# heptaphasis.net
KiCad netlist of a schematic drawn in EAGLE
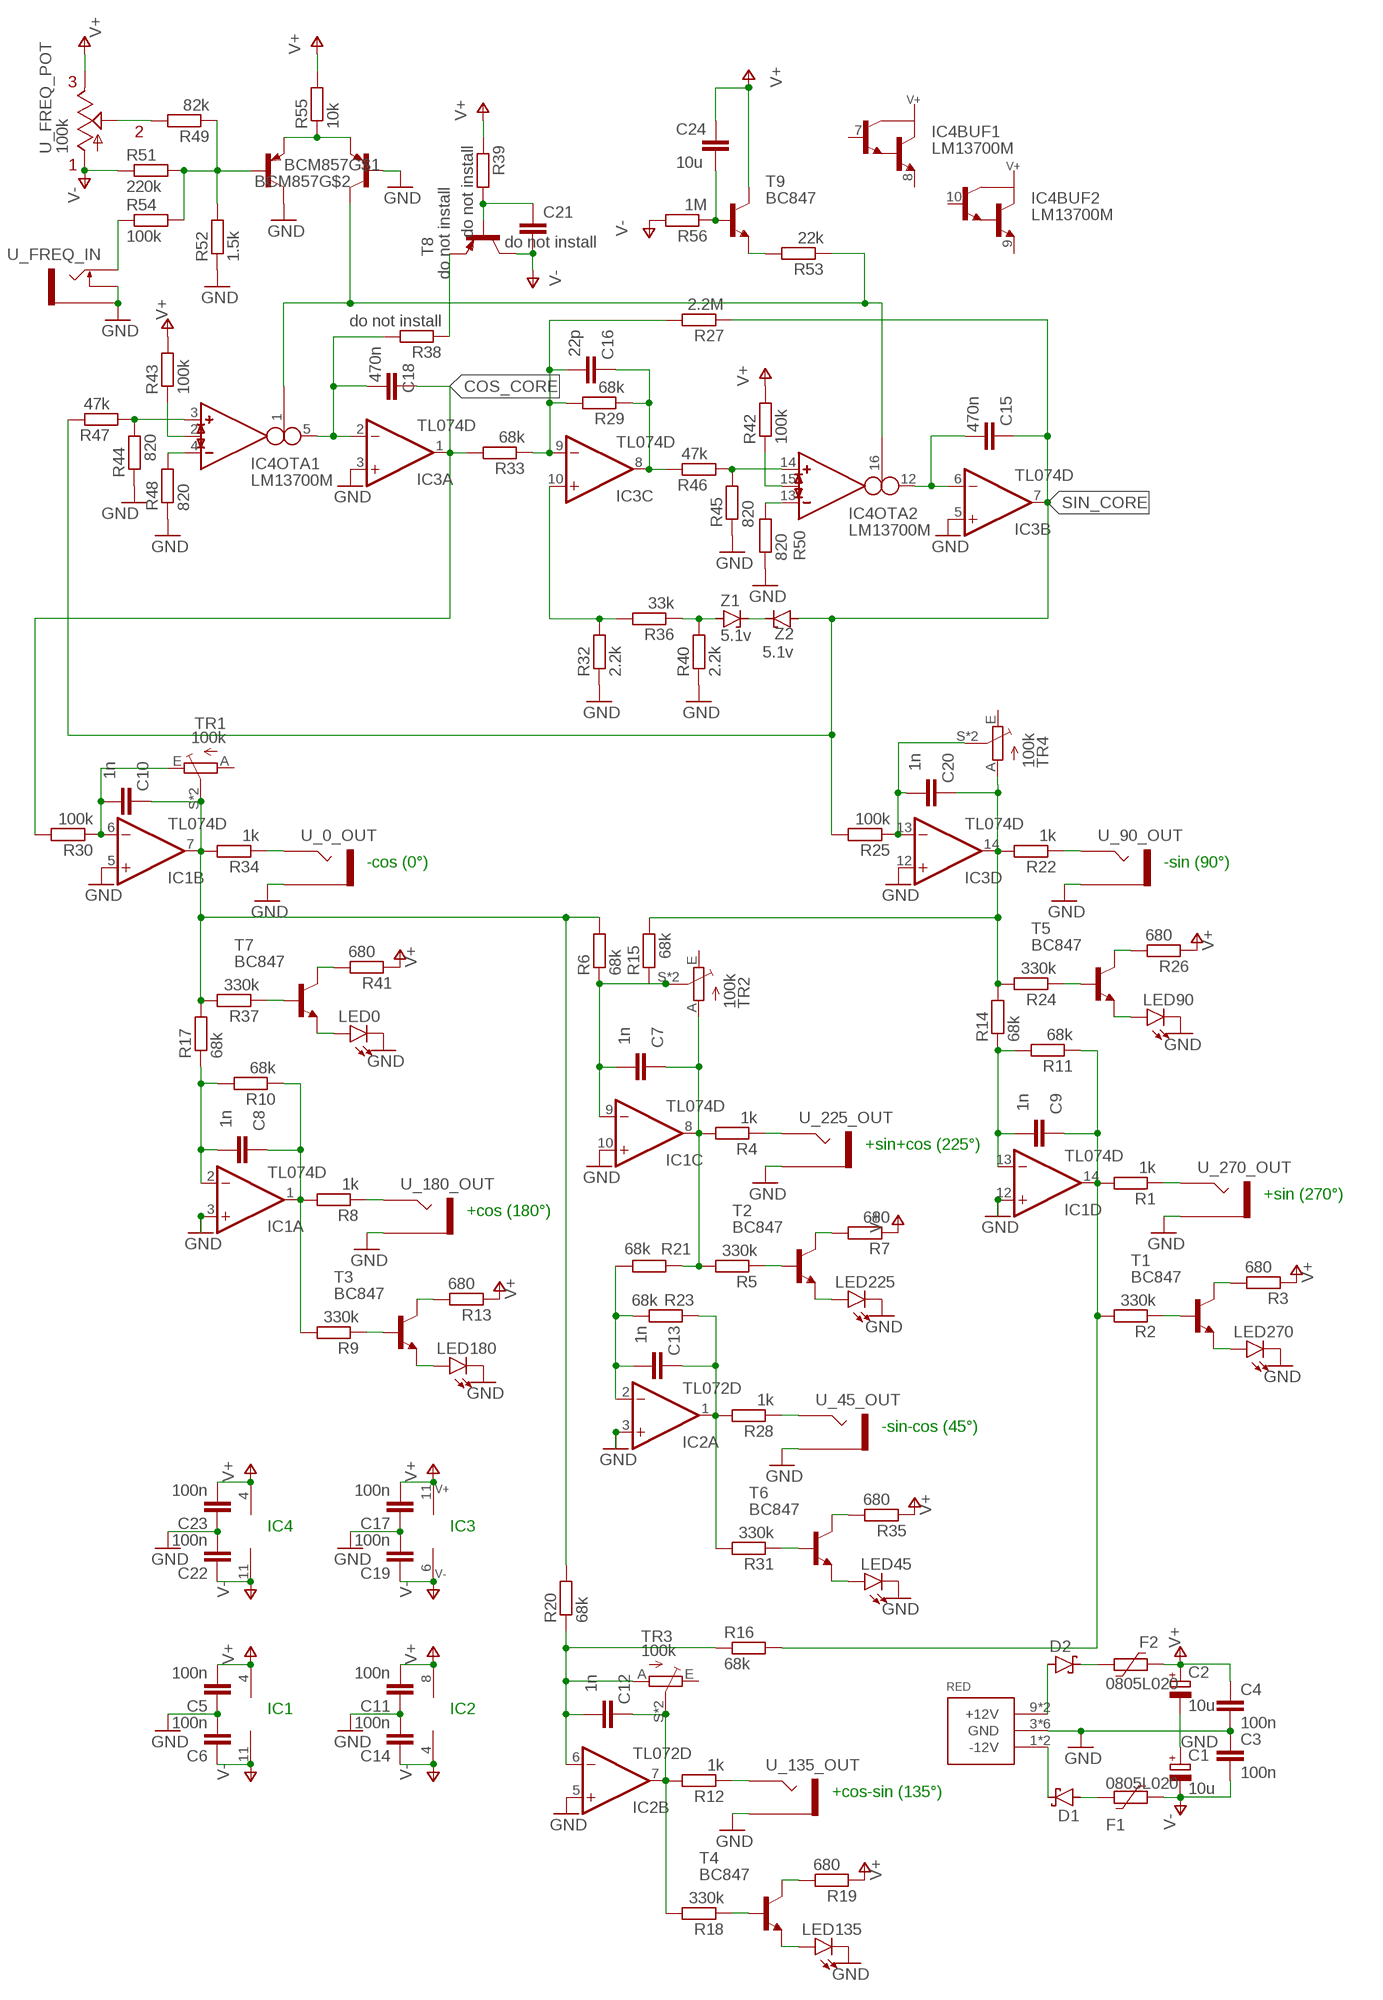
[diagram p0: schematic, sheet 1]

(export (version "E")
  (design (tool "Eeschema 10.0.6"))
  (components
    (comp (ref "BCM857")
      (value "BCM857DS")
      (footprint "eagle-import:SOT457R_PHILIPS")
      (libsource (lib "eagle-import") (part "BCM857DS"))
    )
    (comp (ref "C1")
      (value "10u")
      (footprint "eagle-import:E2-5")
      (libsource (lib "eagle-import") (part "CPOL-EUE2-5"))
    )
    (comp (ref "C2")
      (value "10u")
      (footprint "eagle-import:E2-5")
      (libsource (lib "eagle-import") (part "CPOL-EUE2-5"))
    )
    (comp (ref "C3")
      (value "100n")
      (footprint "eagle-import:C0805")
      (libsource (lib "eagle-import") (part "C-EUC0805"))
    )
    (comp (ref "C4")
      (value "100n")
      (footprint "eagle-import:C0805")
      (libsource (lib "eagle-import") (part "C-EUC0805"))
    )
    (comp (ref "C5")
      (value "100n")
      (footprint "eagle-import:C0805")
      (libsource (lib "eagle-import") (part "C-EUC0805"))
    )
    (comp (ref "C6")
      (value "100n")
      (footprint "eagle-import:C0805")
      (libsource (lib "eagle-import") (part "C-EUC0805"))
    )
    (comp (ref "C7")
      (value "1n")
      (footprint "eagle-import:C0805")
      (libsource (lib "eagle-import") (part "C-EUC0805"))
    )
    (comp (ref "C8")
      (value "1n")
      (footprint "eagle-import:C0805")
      (libsource (lib "eagle-import") (part "C-EUC0805"))
    )
    (comp (ref "C9")
      (value "1n")
      (footprint "eagle-import:C0805")
      (libsource (lib "eagle-import") (part "C-EUC0805"))
    )
    (comp (ref "C10")
      (value "1n")
      (footprint "eagle-import:C0805")
      (libsource (lib "eagle-import") (part "C-EUC0805"))
    )
    (comp (ref "C11")
      (value "100n")
      (footprint "eagle-import:C0805")
      (libsource (lib "eagle-import") (part "C-EUC0805"))
    )
    (comp (ref "C12")
      (value "1n")
      (footprint "eagle-import:C0805")
      (libsource (lib "eagle-import") (part "C-EUC0805"))
    )
    (comp (ref "C13")
      (value "1n")
      (footprint "eagle-import:C0805")
      (libsource (lib "eagle-import") (part "C-EUC0805"))
    )
    (comp (ref "C14")
      (value "100n")
      (footprint "eagle-import:C0805")
      (libsource (lib "eagle-import") (part "C-EUC0805"))
    )
    (comp (ref "C15")
      (value "470n")
      (footprint "eagle-import:C0805")
      (libsource (lib "eagle-import") (part "C-EUC0805"))
    )
    (comp (ref "C16")
      (value "22p")
      (footprint "eagle-import:C0805")
      (libsource (lib "eagle-import") (part "C-EUC0805"))
    )
    (comp (ref "C17")
      (value "100n")
      (footprint "eagle-import:C0805")
      (libsource (lib "eagle-import") (part "C-EUC0805"))
    )
    (comp (ref "C18")
      (value "470n")
      (footprint "eagle-import:C0805")
      (libsource (lib "eagle-import") (part "C-EUC0805"))
    )
    (comp (ref "C19")
      (value "100n")
      (footprint "eagle-import:C0805")
      (libsource (lib "eagle-import") (part "C-EUC0805"))
    )
    (comp (ref "C20")
      (value "1n")
      (footprint "eagle-import:C0805")
      (libsource (lib "eagle-import") (part "C-EUC0805"))
    )
    (comp (ref "C21")
      (value "do not install")
      (footprint "eagle-import:C0805")
      (libsource (lib "eagle-import") (part "C-EUC0805"))
    )
    (comp (ref "C22")
      (value "100n")
      (footprint "eagle-import:C0805")
      (libsource (lib "eagle-import") (part "C-EUC0805"))
    )
    (comp (ref "C23")
      (value "100n")
      (footprint "eagle-import:C0805")
      (libsource (lib "eagle-import") (part "C-EUC0805"))
    )
    (comp (ref "C24")
      (value "10u")
      (footprint "eagle-import:C0805")
      (libsource (lib "eagle-import") (part "C-EUC0805"))
    )
    (comp (ref "D1")
      (value "VERTICAL_SCHOTTKY")
      (footprint "eagle-import:DO41-7")
      (libsource (lib "eagle-import") (part "VERTICAL_SCHOTTKY"))
    )
    (comp (ref "D2")
      (value "VERTICAL_SCHOTTKY")
      (footprint "eagle-import:DO41-7")
      (libsource (lib "eagle-import") (part "VERTICAL_SCHOTTKY"))
    )
    (comp (ref "F1")
      (value "0805L020")
      (footprint "eagle-import:0805L")
      (fields (field (name "MF") "Littelfuse"))
      (libsource (lib "eagle-import") (part "?0805L020"))
    )
    (comp (ref "F2")
      (value "0805L020")
      (footprint "eagle-import:0805L")
      (fields (field (name "MF") "Littelfuse"))
      (libsource (lib "eagle-import") (part "?0805L020"))
    )
    (comp (ref "IC1")
      (value "TL074D")
      (footprint "eagle-import:SO14")
      (libsource (lib "eagle-import") (part "TL074D"))
    )
    (comp (ref "IC2")
      (value "TL072D")
      (footprint "eagle-import:SO08")
      (libsource (lib "eagle-import") (part "TL072D"))
    )
    (comp (ref "IC3")
      (value "TL074D")
      (footprint "eagle-import:SO14")
      (libsource (lib "eagle-import") (part "TL074D"))
    )
    (comp (ref "IC4")
      (value "LM13700M")
      (footprint "eagle-import:SO16")
      (libsource (lib "eagle-import") (part "LM13700M"))
    )
    (comp (ref "LED0")
      (value "LED3MM")
      (footprint "eagle-import:LED3MM")
      (libsource (lib "eagle-import") (part "LED3MM"))
    )
    (comp (ref "LED45")
      (value "LED3MM")
      (footprint "eagle-import:LED3MM")
      (libsource (lib "eagle-import") (part "LED3MM"))
    )
    (comp (ref "LED90")
      (value "LED3MM")
      (footprint "eagle-import:LED3MM")
      (libsource (lib "eagle-import") (part "LED3MM"))
    )
    (comp (ref "LED135")
      (value "LED3MM")
      (footprint "eagle-import:LED3MM")
      (libsource (lib "eagle-import") (part "LED3MM"))
    )
    (comp (ref "LED180")
      (value "LED3MM")
      (footprint "eagle-import:LED3MM")
      (libsource (lib "eagle-import") (part "LED3MM"))
    )
    (comp (ref "LED225")
      (value "LED3MM")
      (footprint "eagle-import:LED3MM")
      (libsource (lib "eagle-import") (part "LED3MM"))
    )
    (comp (ref "LED270")
      (value "LED3MM")
      (footprint "eagle-import:LED3MM")
      (libsource (lib "eagle-import") (part "LED3MM"))
    )
    (comp (ref "R1")
      (value "1k")
      (footprint "eagle-import:R0805")
      (libsource (lib "eagle-import") (part "R-EU_R0805"))
    )
    (comp (ref "R2")
      (value "330k")
      (footprint "eagle-import:R0805")
      (libsource (lib "eagle-import") (part "R-EU_R0805"))
    )
    (comp (ref "R3")
      (value "680")
      (footprint "eagle-import:R0805")
      (libsource (lib "eagle-import") (part "R-EU_R0805"))
    )
    (comp (ref "R4")
      (value "1k")
      (footprint "eagle-import:R0805")
      (libsource (lib "eagle-import") (part "R-EU_R0805"))
    )
    (comp (ref "R5")
      (value "330k")
      (footprint "eagle-import:R0805")
      (libsource (lib "eagle-import") (part "R-EU_R0805"))
    )
    (comp (ref "R6")
      (value "68k")
      (footprint "eagle-import:R0805")
      (libsource (lib "eagle-import") (part "R-EU_R0805"))
    )
    (comp (ref "R7")
      (value "680")
      (footprint "eagle-import:R0805")
      (libsource (lib "eagle-import") (part "R-EU_R0805"))
    )
    (comp (ref "R8")
      (value "1k")
      (footprint "eagle-import:R0805")
      (libsource (lib "eagle-import") (part "R-EU_R0805"))
    )
    (comp (ref "R9")
      (value "330k")
      (footprint "eagle-import:R0805")
      (libsource (lib "eagle-import") (part "R-EU_R0805"))
    )
    (comp (ref "R10")
      (value "68k")
      (footprint "eagle-import:R0805")
      (libsource (lib "eagle-import") (part "R-EU_R0805"))
    )
    (comp (ref "R11")
      (value "68k")
      (footprint "eagle-import:R0805")
      (libsource (lib "eagle-import") (part "R-EU_R0805"))
    )
    (comp (ref "R12")
      (value "1k")
      (footprint "eagle-import:R0805")
      (libsource (lib "eagle-import") (part "R-EU_R0805"))
    )
    (comp (ref "R13")
      (value "680")
      (footprint "eagle-import:R0805")
      (libsource (lib "eagle-import") (part "R-EU_R0805"))
    )
    (comp (ref "R14")
      (value "68k")
      (footprint "eagle-import:R0805")
      (libsource (lib "eagle-import") (part "R-EU_R0805"))
    )
    (comp (ref "R15")
      (value "68k")
      (footprint "eagle-import:R0805")
      (libsource (lib "eagle-import") (part "R-EU_R0805"))
    )
    (comp (ref "R16")
      (value "68k")
      (footprint "eagle-import:R0805")
      (libsource (lib "eagle-import") (part "R-EU_R0805"))
    )
    (comp (ref "R17")
      (value "68k")
      (footprint "eagle-import:R0805")
      (libsource (lib "eagle-import") (part "R-EU_R0805"))
    )
    (comp (ref "R18")
      (value "330k")
      (footprint "eagle-import:R0805")
      (libsource (lib "eagle-import") (part "R-EU_R0805"))
    )
    (comp (ref "R19")
      (value "680")
      (footprint "eagle-import:R0805")
      (libsource (lib "eagle-import") (part "R-EU_R0805"))
    )
    (comp (ref "R20")
      (value "68k")
      (footprint "eagle-import:R0805")
      (libsource (lib "eagle-import") (part "R-EU_R0805"))
    )
    (comp (ref "R21")
      (value "68k")
      (footprint "eagle-import:R0805")
      (libsource (lib "eagle-import") (part "R-EU_R0805"))
    )
    (comp (ref "R22")
      (value "1k")
      (footprint "eagle-import:R0805")
      (libsource (lib "eagle-import") (part "R-EU_R0805"))
    )
    (comp (ref "R23")
      (value "68k")
      (footprint "eagle-import:R0805")
      (libsource (lib "eagle-import") (part "R-EU_R0805"))
    )
    (comp (ref "R24")
      (value "330k")
      (footprint "eagle-import:R0805")
      (libsource (lib "eagle-import") (part "R-EU_R0805"))
    )
    (comp (ref "R25")
      (value "100k")
      (footprint "eagle-import:R0805")
      (libsource (lib "eagle-import") (part "R-EU_R0805"))
    )
    (comp (ref "R26")
      (value "680")
      (footprint "eagle-import:R0805")
      (libsource (lib "eagle-import") (part "R-EU_R0805"))
    )
    (comp (ref "R27")
      (value "2.2M")
      (footprint "eagle-import:R0805")
      (libsource (lib "eagle-import") (part "R-EU_R0805"))
    )
    (comp (ref "R28")
      (value "1k")
      (footprint "eagle-import:R0805")
      (libsource (lib "eagle-import") (part "R-EU_R0805"))
    )
    (comp (ref "R29")
      (value "68k")
      (footprint "eagle-import:R0805")
      (libsource (lib "eagle-import") (part "R-EU_R0805"))
    )
    (comp (ref "R30")
      (value "100k")
      (footprint "eagle-import:R0805")
      (libsource (lib "eagle-import") (part "R-EU_R0805"))
    )
    (comp (ref "R31")
      (value "330k")
      (footprint "eagle-import:R0805")
      (libsource (lib "eagle-import") (part "R-EU_R0805"))
    )
    (comp (ref "R32")
      (value "2.2k")
      (footprint "eagle-import:R0805")
      (libsource (lib "eagle-import") (part "R-EU_R0805"))
    )
    (comp (ref "R33")
      (value "68k")
      (footprint "eagle-import:R0805")
      (libsource (lib "eagle-import") (part "R-EU_R0805"))
    )
    (comp (ref "R34")
      (value "1k")
      (footprint "eagle-import:R0805")
      (libsource (lib "eagle-import") (part "R-EU_R0805"))
    )
    (comp (ref "R35")
      (value "680")
      (footprint "eagle-import:R0805")
      (libsource (lib "eagle-import") (part "R-EU_R0805"))
    )
    (comp (ref "R36")
      (value "33k")
      (footprint "eagle-import:R0805")
      (libsource (lib "eagle-import") (part "R-EU_R0805"))
    )
    (comp (ref "R37")
      (value "330k")
      (footprint "eagle-import:R0805")
      (libsource (lib "eagle-import") (part "R-EU_R0805"))
    )
    (comp (ref "R38")
      (value "do not install")
      (footprint "eagle-import:R0805")
      (libsource (lib "eagle-import") (part "R-EU_R0805"))
    )
    (comp (ref "R39")
      (value "do not install")
      (footprint "eagle-import:R0805")
      (libsource (lib "eagle-import") (part "R-EU_R0805"))
    )
    (comp (ref "R40")
      (value "2.2k")
      (footprint "eagle-import:R0805")
      (libsource (lib "eagle-import") (part "R-EU_R0805"))
    )
    (comp (ref "R41")
      (value "680")
      (footprint "eagle-import:R0805")
      (libsource (lib "eagle-import") (part "R-EU_R0805"))
    )
    (comp (ref "R42")
      (value "100k")
      (footprint "eagle-import:R0805")
      (libsource (lib "eagle-import") (part "R-EU_R0805"))
    )
    (comp (ref "R43")
      (value "100k")
      (footprint "eagle-import:R0805")
      (libsource (lib "eagle-import") (part "R-EU_R0805"))
    )
    (comp (ref "R44")
      (value "820")
      (footprint "eagle-import:R0805")
      (libsource (lib "eagle-import") (part "R-EU_R0805"))
    )
    (comp (ref "R45")
      (value "820")
      (footprint "eagle-import:R0805")
      (libsource (lib "eagle-import") (part "R-EU_R0805"))
    )
    (comp (ref "R46")
      (value "47k")
      (footprint "eagle-import:R0805")
      (libsource (lib "eagle-import") (part "R-EU_R0805"))
    )
    (comp (ref "R47")
      (value "47k")
      (footprint "eagle-import:R0805")
      (libsource (lib "eagle-import") (part "R-EU_R0805"))
    )
    (comp (ref "R48")
      (value "820")
      (footprint "eagle-import:R0805")
      (libsource (lib "eagle-import") (part "R-EU_R0805"))
    )
    (comp (ref "R49")
      (value "82k")
      (footprint "eagle-import:R0805")
      (libsource (lib "eagle-import") (part "R-EU_R0805"))
    )
    (comp (ref "R50")
      (value "820")
      (footprint "eagle-import:R0805")
      (libsource (lib "eagle-import") (part "R-EU_R0805"))
    )
    (comp (ref "R51")
      (value "220k")
      (footprint "eagle-import:R0805")
      (libsource (lib "eagle-import") (part "R-EU_R0805"))
    )
    (comp (ref "R52")
      (value "1.5k")
      (footprint "eagle-import:R0805")
      (libsource (lib "eagle-import") (part "R-EU_R0805"))
    )
    (comp (ref "R53")
      (value "22k")
      (footprint "eagle-import:R0805")
      (libsource (lib "eagle-import") (part "R-EU_R0805"))
    )
    (comp (ref "R54")
      (value "100k")
      (footprint "eagle-import:R0805")
      (libsource (lib "eagle-import") (part "R-EU_R0805"))
    )
    (comp (ref "R55")
      (value "10k")
      (footprint "eagle-import:R0805")
      (libsource (lib "eagle-import") (part "R-EU_R0805"))
    )
    (comp (ref "R56")
      (value "1M")
      (footprint "eagle-import:R0805")
      (libsource (lib "eagle-import") (part "R-EU_R0805"))
    )
    (comp (ref "RED")
      (value "POWER_SIMPLE10")
      (footprint "eagle-import:POWER_10")
      (fields (field (name "SPICEPREFIX") "U"))
      (libsource (lib "eagle-import") (part "POWER_SIMPLE10"))
    )
    (comp (ref "T1")
      (value "BC847")
      (footprint "eagle-import:SOT23")
      (libsource (lib "eagle-import") (part "BC847"))
    )
    (comp (ref "T2")
      (value "BC847")
      (footprint "eagle-import:SOT23")
      (libsource (lib "eagle-import") (part "BC847"))
    )
    (comp (ref "T3")
      (value "BC847")
      (footprint "eagle-import:SOT23")
      (libsource (lib "eagle-import") (part "BC847"))
    )
    (comp (ref "T4")
      (value "BC847")
      (footprint "eagle-import:SOT23")
      (libsource (lib "eagle-import") (part "BC847"))
    )
    (comp (ref "T5")
      (value "BC847")
      (footprint "eagle-import:SOT23")
      (libsource (lib "eagle-import") (part "BC847"))
    )
    (comp (ref "T6")
      (value "BC847")
      (footprint "eagle-import:SOT23")
      (libsource (lib "eagle-import") (part "BC847"))
    )
    (comp (ref "T7")
      (value "BC847")
      (footprint "eagle-import:SOT23")
      (libsource (lib "eagle-import") (part "BC847"))
    )
    (comp (ref "T8")
      (value "do not install")
      (footprint "eagle-import:SOT23")
      (libsource (lib "eagle-import") (part "BC857"))
    )
    (comp (ref "T9")
      (value "BC847")
      (footprint "eagle-import:SOT23")
      (libsource (lib "eagle-import") (part "BC847"))
    )
    (comp (ref "TR1")
      (value "100k")
      (footprint "eagle-import:S64YW")
      (libsource (lib "eagle-import") (part "MULTITURN_TRIMPOT_DUAL_FOOTPRINTS64YW"))
    )
    (comp (ref "TR2")
      (value "100k")
      (footprint "eagle-import:S64YW")
      (libsource (lib "eagle-import") (part "MULTITURN_TRIMPOT_DUAL_FOOTPRINTS64YW"))
    )
    (comp (ref "TR3")
      (value "100k")
      (footprint "eagle-import:S64YW")
      (libsource (lib "eagle-import") (part "MULTITURN_TRIMPOT_DUAL_FOOTPRINTS64YW"))
    )
    (comp (ref "TR4")
      (value "100k")
      (footprint "eagle-import:S64YW")
      (libsource (lib "eagle-import") (part "MULTITURN_TRIMPOT_DUAL_FOOTPRINTS64YW"))
    )
    (comp (ref "U_0_OUT")
      (value "PJ302M_NO_NORM")
      (footprint "eagle-import:PJ302M_NO_NORM")
      (libsource (lib "eagle-import") (part "PJ302M_NO_NORM"))
    )
    (comp (ref "U_45_OUT")
      (value "PJ302M_NO_NORM")
      (footprint "eagle-import:PJ302M_NO_NORM")
      (libsource (lib "eagle-import") (part "PJ302M_NO_NORM"))
    )
    (comp (ref "U_90_OUT")
      (value "PJ302M_NO_NORM")
      (footprint "eagle-import:PJ302M_NO_NORM")
      (libsource (lib "eagle-import") (part "PJ302M_NO_NORM"))
    )
    (comp (ref "U_135_OUT")
      (value "PJ302M_NO_NORM")
      (footprint "eagle-import:PJ302M_NO_NORM")
      (libsource (lib "eagle-import") (part "PJ302M_NO_NORM"))
    )
    (comp (ref "U_180_OUT")
      (value "PJ302M_NO_NORM")
      (footprint "eagle-import:PJ302M_NO_NORM")
      (libsource (lib "eagle-import") (part "PJ302M_NO_NORM"))
    )
    (comp (ref "U_225_OUT")
      (value "PJ302M_NO_NORM")
      (footprint "eagle-import:PJ302M_NO_NORM")
      (libsource (lib "eagle-import") (part "PJ302M_NO_NORM"))
    )
    (comp (ref "U_270_OUT")
      (value "PJ302M_NO_NORM")
      (footprint "eagle-import:PJ302M_NO_NORM")
      (libsource (lib "eagle-import") (part "PJ302M_NO_NORM"))
    )
    (comp (ref "U_FREQ_IN")
      (value "PJ302M")
      (footprint "eagle-import:PJ302M")
      (libsource (lib "eagle-import") (part "PJ302M"))
    )
    (comp (ref "U_FREQ_POT")
      (value "100k")
      (footprint "eagle-import:RK097-SINGLE-ELEMENT")
      (libsource (lib "eagle-import") (part "RK097-SINGLE"))
    )
    (comp (ref "Z1")
      (value "5.1v")
      (footprint "eagle-import:SOD80C")
      (libsource (lib "eagle-import") (part "ZENER-DIODESOD80C"))
    )
    (comp (ref "Z2")
      (value "5.1v")
      (footprint "eagle-import:SOD80C")
      (libsource (lib "eagle-import") (part "ZENER-DIODESOD80C"))
    )
  )
  (nets
    (net (code "1") (name "COS_CORE") (class "Default")
      (node (ref "C18") (pin "1") (pinfunction "1_1") (pintype "passive"))
      (node (ref "IC3") (pin "1") (pinfunction "OUT_1") (pintype "output"))
      (node (ref "R30") (pin "2") (pinfunction "2_2") (pintype "passive"))
      (node (ref "R33") (pin "2") (pinfunction "2_2") (pintype "passive"))
    )
    (net (code "2") (name "GND") (class "Default")
      (node (ref "BCM857") (pin "5") (pinfunction "B_5") (pintype "passive"))
      (node (ref "BCM857") (pin "6") (pinfunction "C_6") (pintype "passive"))
      (node (ref "C1") (pin "+") (pinfunction "+_+") (pintype "passive"))
      (node (ref "C11") (pin "1") (pinfunction "1_1") (pintype "passive"))
      (node (ref "C14") (pin "2") (pinfunction "2_2") (pintype "passive"))
      (node (ref "C17") (pin "1") (pinfunction "1_1") (pintype "passive"))
      (node (ref "C19") (pin "2") (pinfunction "2_2") (pintype "passive"))
      (node (ref "C2") (pin "-") (pinfunction "-_-") (pintype "passive"))
      (node (ref "C22") (pin "2") (pinfunction "2_2") (pintype "passive"))
      (node (ref "C23") (pin "1") (pinfunction "1_1") (pintype "passive"))
      (node (ref "C3") (pin "1") (pinfunction "1_1") (pintype "passive"))
      (node (ref "C4") (pin "2") (pinfunction "2_2") (pintype "passive"))
      (node (ref "C5") (pin "1") (pinfunction "1_1") (pintype "passive"))
      (node (ref "C6") (pin "2") (pinfunction "2_2") (pintype "passive"))
      (node (ref "IC1") (pin "10") (pinfunction "+IN_10") (pintype "input"))
      (node (ref "IC1") (pin "12") (pinfunction "+IN_12") (pintype "input"))
      (node (ref "IC1") (pin "3") (pinfunction "+IN_3") (pintype "input"))
      (node (ref "IC1") (pin "5") (pinfunction "+IN_5") (pintype "input"))
      (node (ref "IC2") (pin "3") (pinfunction "+IN_3") (pintype "input"))
      (node (ref "IC2") (pin "5") (pinfunction "+IN_5") (pintype "input"))
      (node (ref "IC3") (pin "12") (pinfunction "+IN_12") (pintype "input"))
      (node (ref "IC3") (pin "3") (pinfunction "+IN_3") (pintype "input"))
      (node (ref "IC3") (pin "5") (pinfunction "+IN_5") (pintype "input"))
      (node (ref "LED0") (pin "K") (pinfunction "C_K") (pintype "passive"))
      (node (ref "LED135") (pin "K") (pinfunction "C_K") (pintype "passive"))
      (node (ref "LED180") (pin "K") (pinfunction "C_K") (pintype "passive"))
      (node (ref "LED225") (pin "K") (pinfunction "C_K") (pintype "passive"))
      (node (ref "LED270") (pin "K") (pinfunction "C_K") (pintype "passive"))
      (node (ref "LED45") (pin "K") (pinfunction "C_K") (pintype "passive"))
      (node (ref "LED90") (pin "K") (pinfunction "C_K") (pintype "passive"))
      (node (ref "R32") (pin "1") (pinfunction "1_1") (pintype "passive"))
      (node (ref "R40") (pin "1") (pinfunction "1_1") (pintype "passive"))
      (node (ref "R44") (pin "1") (pinfunction "1_1") (pintype "passive"))
      (node (ref "R45") (pin "1") (pinfunction "1_1") (pintype "passive"))
      (node (ref "R48") (pin "1") (pinfunction "1_1") (pintype "passive"))
      (node (ref "R50") (pin "1") (pinfunction "1_1") (pintype "passive"))
      (node (ref "R52") (pin "1") (pinfunction "1_1") (pintype "passive"))
      (node (ref "RED") (pin "3") (pinfunction "GND_3") (pintype "bidirectional"))
      (node (ref "RED") (pin "4") (pinfunction "GND_4") (pintype "bidirectional"))
      (node (ref "RED") (pin "5") (pinfunction "GND_5") (pintype "bidirectional"))
      (node (ref "RED") (pin "6") (pinfunction "GND_6") (pintype "bidirectional"))
      (node (ref "RED") (pin "7") (pinfunction "GND_7") (pintype "bidirectional"))
      (node (ref "RED") (pin "8") (pinfunction "GND_8") (pintype "bidirectional"))
      (node (ref "U_0_OUT") (pin "GND") (pinfunction "SLEEVE_GND") (pintype "passive"))
      (node (ref "U_135_OUT") (pin "GND") (pinfunction "SLEEVE_GND") (pintype "passive"))
      (node (ref "U_180_OUT") (pin "GND") (pinfunction "SLEEVE_GND") (pintype "passive"))
      (node (ref "U_225_OUT") (pin "GND") (pinfunction "SLEEVE_GND") (pintype "passive"))
      (node (ref "U_270_OUT") (pin "GND") (pinfunction "SLEEVE_GND") (pintype "passive"))
      (node (ref "U_45_OUT") (pin "GND") (pinfunction "SLEEVE_GND") (pintype "passive"))
      (node (ref "U_90_OUT") (pin "GND") (pinfunction "SLEEVE_GND") (pintype "passive"))
      (node (ref "U_FREQ_IN") (pin "GND") (pinfunction "SLEEVE_GND") (pintype "passive"))
      (node (ref "U_FREQ_IN") (pin "SW") (pinfunction "SWITCH_SW") (pintype "passive"))
    )
    (net (code "3") (name "Net-(BCM857A-B)") (class "Default")
      (node (ref "BCM857") (pin "2") (pinfunction "B_2") (pintype "passive"))
      (node (ref "R49") (pin "1") (pinfunction "1_1") (pintype "passive"))
      (node (ref "R51") (pin "2") (pinfunction "2_2") (pintype "passive"))
      (node (ref "R52") (pin "2") (pinfunction "2_2") (pintype "passive"))
      (node (ref "R54") (pin "2") (pinfunction "2_2") (pintype "passive"))
    )
    (net (code "4") (name "Net-(BCM857A-E)") (class "Default")
      (node (ref "BCM857") (pin "1") (pinfunction "E_1") (pintype "passive"))
      (node (ref "BCM857") (pin "4") (pinfunction "E_4") (pintype "passive"))
      (node (ref "R55") (pin "1") (pinfunction "1_1") (pintype "passive"))
    )
    (net (code "5") (name "Net-(BCM857B-C)") (class "Default")
      (node (ref "BCM857") (pin "3") (pinfunction "C_3") (pintype "passive"))
      (node (ref "IC4") (pin "1") (pinfunction "I_BIAS_1") (pintype "input"))
      (node (ref "IC4") (pin "16") (pinfunction "I_BIAS_16") (pintype "input"))
      (node (ref "R53") (pin "1") (pinfunction "1_1") (pintype "passive"))
    )
    (net (code "6") (name "Net-(D1-PadA)") (class "Default")
      (node (ref "D1") (pin "A") (pinfunction "A_A") (pintype "passive"))
      (node (ref "F1") (pin "2") (pinfunction "2_2") (pintype "passive"))
    )
    (net (code "7") (name "Net-(D1-PadC)") (class "Default")
      (node (ref "D1") (pin "C") (pinfunction "C_C") (pintype "passive"))
      (node (ref "RED") (pin "1") (pinfunction "-12V_1") (pintype "bidirectional"))
      (node (ref "RED") (pin "2") (pinfunction "-12V_2") (pintype "bidirectional"))
    )
    (net (code "8") (name "Net-(D2-PadA)") (class "Default")
      (node (ref "D2") (pin "A") (pinfunction "A_A") (pintype "passive"))
      (node (ref "RED") (pin "10") (pinfunction "+12V_10") (pintype "bidirectional"))
      (node (ref "RED") (pin "9") (pinfunction "+12V_9") (pintype "bidirectional"))
    )
    (net (code "9") (name "Net-(D2-PadC)") (class "Default")
      (node (ref "D2") (pin "C") (pinfunction "C_C") (pintype "passive"))
      (node (ref "F2") (pin "2") (pinfunction "2_2") (pintype "passive"))
    )
    (net (code "10") (name "Net-(IC1A--IN)") (class "Default")
      (node (ref "C8") (pin "2") (pinfunction "2_2") (pintype "passive"))
      (node (ref "IC1") (pin "2") (pinfunction "-IN_2") (pintype "input"))
      (node (ref "R10") (pin "2") (pinfunction "2_2") (pintype "passive"))
      (node (ref "R17") (pin "1") (pinfunction "1_1") (pintype "passive"))
    )
    (net (code "11") (name "Net-(IC1A-OUT)") (class "Default")
      (node (ref "C8") (pin "1") (pinfunction "1_1") (pintype "passive"))
      (node (ref "IC1") (pin "1") (pinfunction "OUT_1") (pintype "output"))
      (node (ref "R10") (pin "1") (pinfunction "1_1") (pintype "passive"))
      (node (ref "R8") (pin "2") (pinfunction "2_2") (pintype "passive"))
      (node (ref "R9") (pin "2") (pinfunction "2_2") (pintype "passive"))
    )
    (net (code "12") (name "Net-(IC1B--IN)") (class "Default")
      (node (ref "C10") (pin "2") (pinfunction "2_2") (pintype "passive"))
      (node (ref "IC1") (pin "6") (pinfunction "-IN_6") (pintype "input"))
      (node (ref "R30") (pin "1") (pinfunction "1_1") (pintype "passive"))
      (node (ref "TR1") (pin "E") (pinfunction "E_E") (pintype "passive"))
    )
    (net (code "13") (name "Net-(IC1B-OUT)") (class "Default")
      (node (ref "C10") (pin "1") (pinfunction "1_1") (pintype "passive"))
      (node (ref "IC1") (pin "7") (pinfunction "OUT_7") (pintype "output"))
      (node (ref "R17") (pin "2") (pinfunction "2_2") (pintype "passive"))
      (node (ref "R20") (pin "2") (pinfunction "2_2") (pintype "passive"))
      (node (ref "R34") (pin "2") (pinfunction "2_2") (pintype "passive"))
      (node (ref "R37") (pin "2") (pinfunction "2_2") (pintype "passive"))
      (node (ref "R6") (pin "2") (pinfunction "2_2") (pintype "passive"))
      (node (ref "TR1") (pin "S") (pinfunction "S_S") (pintype "passive"))
      (node (ref "TR1") (pin "S@1") (pinfunction "S_S@1") (pintype "passive"))
    )
    (net (code "14") (name "Net-(IC1C--IN)") (class "Default")
      (node (ref "C7") (pin "2") (pinfunction "2_2") (pintype "passive"))
      (node (ref "IC1") (pin "9") (pinfunction "-IN_9") (pintype "input"))
      (node (ref "R15") (pin "1") (pinfunction "1_1") (pintype "passive"))
      (node (ref "R6") (pin "1") (pinfunction "1_1") (pintype "passive"))
      (node (ref "TR2") (pin "S") (pinfunction "S_S") (pintype "passive"))
      (node (ref "TR2") (pin "S@1") (pinfunction "S_S@1") (pintype "passive"))
    )
    (net (code "15") (name "Net-(IC1C-OUT)") (class "Default")
      (node (ref "C7") (pin "1") (pinfunction "1_1") (pintype "passive"))
      (node (ref "IC1") (pin "8") (pinfunction "OUT_8") (pintype "output"))
      (node (ref "R21") (pin "2") (pinfunction "2_2") (pintype "passive"))
      (node (ref "R4") (pin "2") (pinfunction "2_2") (pintype "passive"))
      (node (ref "R5") (pin "2") (pinfunction "2_2") (pintype "passive"))
      (node (ref "TR2") (pin "A") (pinfunction "A_A") (pintype "passive"))
    )
    (net (code "16") (name "Net-(IC1D--IN)") (class "Default")
      (node (ref "C9") (pin "2") (pinfunction "2_2") (pintype "passive"))
      (node (ref "IC1") (pin "13") (pinfunction "-IN_13") (pintype "input"))
      (node (ref "R11") (pin "2") (pinfunction "2_2") (pintype "passive"))
      (node (ref "R14") (pin "1") (pinfunction "1_1") (pintype "passive"))
    )
    (net (code "17") (name "Net-(IC1D-OUT)") (class "Default")
      (node (ref "C9") (pin "1") (pinfunction "1_1") (pintype "passive"))
      (node (ref "IC1") (pin "14") (pinfunction "OUT_14") (pintype "output"))
      (node (ref "R1") (pin "2") (pinfunction "2_2") (pintype "passive"))
      (node (ref "R11") (pin "1") (pinfunction "1_1") (pintype "passive"))
      (node (ref "R16") (pin "2") (pinfunction "2_2") (pintype "passive"))
      (node (ref "R2") (pin "2") (pinfunction "2_2") (pintype "passive"))
    )
    (net (code "18") (name "Net-(IC2A--IN)") (class "Default")
      (node (ref "C13") (pin "2") (pinfunction "2_2") (pintype "passive"))
      (node (ref "IC2") (pin "2") (pinfunction "-IN_2") (pintype "input"))
      (node (ref "R21") (pin "1") (pinfunction "1_1") (pintype "passive"))
      (node (ref "R23") (pin "2") (pinfunction "2_2") (pintype "passive"))
    )
    (net (code "19") (name "Net-(IC2A-OUT)") (class "Default")
      (node (ref "C13") (pin "1") (pinfunction "1_1") (pintype "passive"))
      (node (ref "IC2") (pin "1") (pinfunction "OUT_1") (pintype "output"))
      (node (ref "R23") (pin "1") (pinfunction "1_1") (pintype "passive"))
      (node (ref "R28") (pin "2") (pinfunction "2_2") (pintype "passive"))
      (node (ref "R31") (pin "2") (pinfunction "2_2") (pintype "passive"))
    )
    (net (code "20") (name "Net-(IC2B--IN)") (class "Default")
      (node (ref "C12") (pin "2") (pinfunction "2_2") (pintype "passive"))
      (node (ref "IC2") (pin "6") (pinfunction "-IN_6") (pintype "input"))
      (node (ref "R16") (pin "1") (pinfunction "1_1") (pintype "passive"))
      (node (ref "R20") (pin "1") (pinfunction "1_1") (pintype "passive"))
      (node (ref "TR3") (pin "A") (pinfunction "A_A") (pintype "passive"))
    )
    (net (code "21") (name "Net-(IC2B-OUT)") (class "Default")
      (node (ref "C12") (pin "1") (pinfunction "1_1") (pintype "passive"))
      (node (ref "IC2") (pin "7") (pinfunction "OUT_7") (pintype "output"))
      (node (ref "R12") (pin "2") (pinfunction "2_2") (pintype "passive"))
      (node (ref "R18") (pin "2") (pinfunction "2_2") (pintype "passive"))
      (node (ref "TR3") (pin "S") (pinfunction "S_S") (pintype "passive"))
      (node (ref "TR3") (pin "S@1") (pinfunction "S_S@1") (pintype "passive"))
    )
    (net (code "22") (name "Net-(IC3A--IN)") (class "Default")
      (node (ref "C18") (pin "2") (pinfunction "2_2") (pintype "passive"))
      (node (ref "IC3") (pin "2") (pinfunction "-IN_2") (pintype "input"))
      (node (ref "IC4") (pin "5") (pinfunction "OUT_5") (pintype "output"))
      (node (ref "R38") (pin "2") (pinfunction "2_2") (pintype "passive"))
    )
    (net (code "23") (name "Net-(IC3B--IN)") (class "Default")
      (node (ref "C15") (pin "2") (pinfunction "2_2") (pintype "passive"))
      (node (ref "IC3") (pin "6") (pinfunction "-IN_6") (pintype "input"))
      (node (ref "IC4") (pin "12") (pinfunction "OUT_12") (pintype "output"))
    )
    (net (code "24") (name "Net-(IC3C-+IN)") (class "Default")
      (node (ref "IC3") (pin "10") (pinfunction "+IN_10") (pintype "input"))
      (node (ref "R32") (pin "2") (pinfunction "2_2") (pintype "passive"))
      (node (ref "R36") (pin "2") (pinfunction "2_2") (pintype "passive"))
    )
    (net (code "25") (name "Net-(IC3C--IN)") (class "Default")
      (node (ref "C16") (pin "2") (pinfunction "2_2") (pintype "passive"))
      (node (ref "IC3") (pin "9") (pinfunction "-IN_9") (pintype "input"))
      (node (ref "R27") (pin "2") (pinfunction "2_2") (pintype "passive"))
      (node (ref "R29") (pin "2") (pinfunction "2_2") (pintype "passive"))
      (node (ref "R33") (pin "1") (pinfunction "1_1") (pintype "passive"))
    )
    (net (code "26") (name "Net-(IC3C-OUT)") (class "Default")
      (node (ref "C16") (pin "1") (pinfunction "1_1") (pintype "passive"))
      (node (ref "IC3") (pin "8") (pinfunction "OUT_8") (pintype "output"))
      (node (ref "R29") (pin "1") (pinfunction "1_1") (pintype "passive"))
      (node (ref "R46") (pin "2") (pinfunction "2_2") (pintype "passive"))
    )
    (net (code "27") (name "Net-(IC3D--IN)") (class "Default")
      (node (ref "C20") (pin "2") (pinfunction "2_2") (pintype "passive"))
      (node (ref "IC3") (pin "13") (pinfunction "-IN_13") (pintype "input"))
      (node (ref "R25") (pin "1") (pinfunction "1_1") (pintype "passive"))
      (node (ref "TR4") (pin "S") (pinfunction "S_S") (pintype "passive"))
      (node (ref "TR4") (pin "S@1") (pinfunction "S_S@1") (pintype "passive"))
    )
    (net (code "28") (name "Net-(IC3D-OUT)") (class "Default")
      (node (ref "C20") (pin "1") (pinfunction "1_1") (pintype "passive"))
      (node (ref "IC3") (pin "14") (pinfunction "OUT_14") (pintype "output"))
      (node (ref "R14") (pin "2") (pinfunction "2_2") (pintype "passive"))
      (node (ref "R15") (pin "2") (pinfunction "2_2") (pintype "passive"))
      (node (ref "R22") (pin "2") (pinfunction "2_2") (pintype "passive"))
      (node (ref "R24") (pin "2") (pinfunction "2_2") (pintype "passive"))
      (node (ref "TR4") (pin "A") (pinfunction "A_A") (pintype "passive"))
    )
    (net (code "29") (name "Net-(IC4C-IN_N)") (class "Default")
      (node (ref "IC4") (pin "4") (pinfunction "IN_N_4") (pintype "input"))
      (node (ref "R48") (pin "2") (pinfunction "2_2") (pintype "passive"))
    )
    (net (code "30") (name "Net-(IC4C-IN_P)") (class "Default")
      (node (ref "IC4") (pin "3") (pinfunction "IN_P_3") (pintype "input"))
      (node (ref "R44") (pin "2") (pinfunction "2_2") (pintype "passive"))
      (node (ref "R47") (pin "1") (pinfunction "1_1") (pintype "passive"))
    )
    (net (code "31") (name "Net-(IC4C-I_DIODE)") (class "Default")
      (node (ref "IC4") (pin "2") (pinfunction "I_DIODE_2") (pintype "input"))
      (node (ref "R43") (pin "1") (pinfunction "1_1") (pintype "passive"))
    )
    (net (code "32") (name "Net-(IC4D-IN_N)") (class "Default")
      (node (ref "IC4") (pin "13") (pinfunction "IN_N_13") (pintype "input"))
      (node (ref "R50") (pin "2") (pinfunction "2_2") (pintype "passive"))
    )
    (net (code "33") (name "Net-(IC4D-IN_P)") (class "Default")
      (node (ref "IC4") (pin "14") (pinfunction "IN_P_14") (pintype "input"))
      (node (ref "R45") (pin "2") (pinfunction "2_2") (pintype "passive"))
      (node (ref "R46") (pin "1") (pinfunction "1_1") (pintype "passive"))
    )
    (net (code "34") (name "Net-(IC4D-I_DIODE)") (class "Default")
      (node (ref "IC4") (pin "15") (pinfunction "I_DIODE_15") (pintype "input"))
      (node (ref "R42") (pin "1") (pinfunction "1_1") (pintype "passive"))
    )
    (net (code "35") (name "Net-(R1-Pad1)") (class "Default")
      (node (ref "R1") (pin "1") (pinfunction "1_1") (pintype "passive"))
      (node (ref "U_270_OUT") (pin "TIP") (pinfunction "TIP_TIP") (pintype "passive"))
    )
    (net (code "36") (name "Net-(R4-Pad1)") (class "Default")
      (node (ref "R4") (pin "1") (pinfunction "1_1") (pintype "passive"))
      (node (ref "U_225_OUT") (pin "TIP") (pinfunction "TIP_TIP") (pintype "passive"))
    )
    (net (code "37") (name "Net-(R8-Pad1)") (class "Default")
      (node (ref "R8") (pin "1") (pinfunction "1_1") (pintype "passive"))
      (node (ref "U_180_OUT") (pin "TIP") (pinfunction "TIP_TIP") (pintype "passive"))
    )
    (net (code "38") (name "Net-(R12-Pad1)") (class "Default")
      (node (ref "R12") (pin "1") (pinfunction "1_1") (pintype "passive"))
      (node (ref "U_135_OUT") (pin "TIP") (pinfunction "TIP_TIP") (pintype "passive"))
    )
    (net (code "39") (name "Net-(R22-Pad1)") (class "Default")
      (node (ref "R22") (pin "1") (pinfunction "1_1") (pintype "passive"))
      (node (ref "U_90_OUT") (pin "TIP") (pinfunction "TIP_TIP") (pintype "passive"))
    )
    (net (code "40") (name "Net-(R28-Pad1)") (class "Default")
      (node (ref "R28") (pin "1") (pinfunction "1_1") (pintype "passive"))
      (node (ref "U_45_OUT") (pin "TIP") (pinfunction "TIP_TIP") (pintype "passive"))
    )
    (net (code "41") (name "Net-(R34-Pad1)") (class "Default")
      (node (ref "R34") (pin "1") (pinfunction "1_1") (pintype "passive"))
      (node (ref "U_0_OUT") (pin "TIP") (pinfunction "TIP_TIP") (pintype "passive"))
    )
    (net (code "42") (name "Net-(R36-Pad1)") (class "Default")
      (node (ref "R36") (pin "1") (pinfunction "1_1") (pintype "passive"))
      (node (ref "R40") (pin "2") (pinfunction "2_2") (pintype "passive"))
      (node (ref "Z1") (pin "A") (pinfunction "A_A") (pintype "passive"))
    )
    (net (code "43") (name "Net-(R54-Pad1)") (class "Default")
      (node (ref "R54") (pin "1") (pinfunction "1_1") (pintype "passive"))
      (node (ref "U_FREQ_IN") (pin "TIP") (pinfunction "TIP_TIP") (pintype "passive"))
    )
    (net (code "44") (name "Net-(T1-B)") (class "Default")
      (node (ref "R2") (pin "1") (pinfunction "1_1") (pintype "passive"))
      (node (ref "T1") (pin "1") (pinfunction "B_1") (pintype "passive"))
    )
    (net (code "45") (name "Net-(T1-C)") (class "Default")
      (node (ref "R3") (pin "2") (pinfunction "2_2") (pintype "passive"))
      (node (ref "T1") (pin "3") (pinfunction "C_3") (pintype "passive"))
    )
    (net (code "46") (name "Net-(T1-E)") (class "Default")
      (node (ref "LED270") (pin "A") (pinfunction "A_A") (pintype "passive"))
      (node (ref "T1") (pin "2") (pinfunction "E_2") (pintype "passive"))
    )
    (net (code "47") (name "Net-(T2-B)") (class "Default")
      (node (ref "R5") (pin "1") (pinfunction "1_1") (pintype "passive"))
      (node (ref "T2") (pin "1") (pinfunction "B_1") (pintype "passive"))
    )
    (net (code "48") (name "Net-(T2-C)") (class "Default")
      (node (ref "R7") (pin "2") (pinfunction "2_2") (pintype "passive"))
      (node (ref "T2") (pin "3") (pinfunction "C_3") (pintype "passive"))
    )
    (net (code "49") (name "Net-(T2-E)") (class "Default")
      (node (ref "LED225") (pin "A") (pinfunction "A_A") (pintype "passive"))
      (node (ref "T2") (pin "2") (pinfunction "E_2") (pintype "passive"))
    )
    (net (code "50") (name "Net-(T3-B)") (class "Default")
      (node (ref "R9") (pin "1") (pinfunction "1_1") (pintype "passive"))
      (node (ref "T3") (pin "1") (pinfunction "B_1") (pintype "passive"))
    )
    (net (code "51") (name "Net-(T3-C)") (class "Default")
      (node (ref "R13") (pin "2") (pinfunction "2_2") (pintype "passive"))
      (node (ref "T3") (pin "3") (pinfunction "C_3") (pintype "passive"))
    )
    (net (code "52") (name "Net-(T3-E)") (class "Default")
      (node (ref "LED180") (pin "A") (pinfunction "A_A") (pintype "passive"))
      (node (ref "T3") (pin "2") (pinfunction "E_2") (pintype "passive"))
    )
    (net (code "53") (name "Net-(T4-B)") (class "Default")
      (node (ref "R18") (pin "1") (pinfunction "1_1") (pintype "passive"))
      (node (ref "T4") (pin "1") (pinfunction "B_1") (pintype "passive"))
    )
    (net (code "54") (name "Net-(T4-C)") (class "Default")
      (node (ref "R19") (pin "2") (pinfunction "2_2") (pintype "passive"))
      (node (ref "T4") (pin "3") (pinfunction "C_3") (pintype "passive"))
    )
    (net (code "55") (name "Net-(T4-E)") (class "Default")
      (node (ref "LED135") (pin "A") (pinfunction "A_A") (pintype "passive"))
      (node (ref "T4") (pin "2") (pinfunction "E_2") (pintype "passive"))
    )
    (net (code "56") (name "Net-(T5-B)") (class "Default")
      (node (ref "R24") (pin "1") (pinfunction "1_1") (pintype "passive"))
      (node (ref "T5") (pin "1") (pinfunction "B_1") (pintype "passive"))
    )
    (net (code "57") (name "Net-(T5-C)") (class "Default")
      (node (ref "R26") (pin "2") (pinfunction "2_2") (pintype "passive"))
      (node (ref "T5") (pin "3") (pinfunction "C_3") (pintype "passive"))
    )
    (net (code "58") (name "Net-(T5-E)") (class "Default")
      (node (ref "LED90") (pin "A") (pinfunction "A_A") (pintype "passive"))
      (node (ref "T5") (pin "2") (pinfunction "E_2") (pintype "passive"))
    )
    (net (code "59") (name "Net-(T6-B)") (class "Default")
      (node (ref "R31") (pin "1") (pinfunction "1_1") (pintype "passive"))
      (node (ref "T6") (pin "1") (pinfunction "B_1") (pintype "passive"))
    )
    (net (code "60") (name "Net-(T6-C)") (class "Default")
      (node (ref "R35") (pin "2") (pinfunction "2_2") (pintype "passive"))
      (node (ref "T6") (pin "3") (pinfunction "C_3") (pintype "passive"))
    )
    (net (code "61") (name "Net-(T6-E)") (class "Default")
      (node (ref "LED45") (pin "A") (pinfunction "A_A") (pintype "passive"))
      (node (ref "T6") (pin "2") (pinfunction "E_2") (pintype "passive"))
    )
    (net (code "62") (name "Net-(T7-B)") (class "Default")
      (node (ref "R37") (pin "1") (pinfunction "1_1") (pintype "passive"))
      (node (ref "T7") (pin "1") (pinfunction "B_1") (pintype "passive"))
    )
    (net (code "63") (name "Net-(T7-C)") (class "Default")
      (node (ref "R41") (pin "2") (pinfunction "2_2") (pintype "passive"))
      (node (ref "T7") (pin "3") (pinfunction "C_3") (pintype "passive"))
    )
    (net (code "64") (name "Net-(T7-E)") (class "Default")
      (node (ref "LED0") (pin "A") (pinfunction "A_A") (pintype "passive"))
      (node (ref "T7") (pin "2") (pinfunction "E_2") (pintype "passive"))
    )
    (net (code "65") (name "Net-(T8-B)") (class "Default")
      (node (ref "C21") (pin "1") (pinfunction "1_1") (pintype "passive"))
      (node (ref "R39") (pin "2") (pinfunction "2_2") (pintype "passive"))
      (node (ref "T8") (pin "1") (pinfunction "B_1") (pintype "passive"))
    )
    (net (code "66") (name "Net-(T8-E)") (class "Default")
      (node (ref "R38") (pin "1") (pinfunction "1_1") (pintype "passive"))
      (node (ref "T8") (pin "2") (pinfunction "E_2") (pintype "passive"))
    )
    (net (code "67") (name "Net-(T9-B)") (class "Default")
      (node (ref "C24") (pin "2") (pinfunction "2_2") (pintype "passive"))
      (node (ref "R56") (pin "1") (pinfunction "1_1") (pintype "passive"))
      (node (ref "T9") (pin "1") (pinfunction "B_1") (pintype "passive"))
    )
    (net (code "68") (name "Net-(T9-E)") (class "Default")
      (node (ref "R53") (pin "2") (pinfunction "2_2") (pintype "passive"))
      (node (ref "T9") (pin "2") (pinfunction "E_2") (pintype "passive"))
    )
    (net (code "69") (name "Net-(U_FREQ_POT-S)") (class "Default")
      (node (ref "R49") (pin "2") (pinfunction "2_2") (pintype "passive"))
      (node (ref "U_FREQ_POT") (pin "P$5") (pinfunction "S_P$5") (pintype "passive"))
    )
    (net (code "70") (name "Net-(Z1-PadC)") (class "Default")
      (node (ref "Z1") (pin "C") (pinfunction "C_C") (pintype "passive"))
      (node (ref "Z2") (pin "C") (pinfunction "C_C") (pintype "passive"))
    )
    (net (code "71") (name "SIN_CORE") (class "Default")
      (node (ref "C15") (pin "1") (pinfunction "1_1") (pintype "passive"))
      (node (ref "IC3") (pin "7") (pinfunction "OUT_7") (pintype "output"))
      (node (ref "R25") (pin "2") (pinfunction "2_2") (pintype "passive"))
      (node (ref "R27") (pin "1") (pinfunction "1_1") (pintype "passive"))
      (node (ref "R47") (pin "2") (pinfunction "2_2") (pintype "passive"))
      (node (ref "Z2") (pin "A") (pinfunction "A_A") (pintype "passive"))
    )
    (net (code "72") (name "V+") (class "Default")
      (node (ref "C11") (pin "2") (pinfunction "2_2") (pintype "passive"))
      (node (ref "C17") (pin "2") (pinfunction "2_2") (pintype "passive"))
      (node (ref "C2") (pin "+") (pinfunction "+_+") (pintype "passive"))
      (node (ref "C23") (pin "2") (pinfunction "2_2") (pintype "passive"))
      (node (ref "C24") (pin "1") (pinfunction "1_1") (pintype "passive"))
      (node (ref "C4") (pin "1") (pinfunction "1_1") (pintype "passive"))
      (node (ref "C5") (pin "2") (pinfunction "2_2") (pintype "passive"))
      (node (ref "F2") (pin "1") (pinfunction "1_1") (pintype "passive"))
      (node (ref "IC1") (pin "4") (pinfunction "V+_4") (pintype "power_in"))
      (node (ref "IC2") (pin "8") (pinfunction "V+_8") (pintype "power_in"))
      (node (ref "IC3") (pin "4") (pinfunction "V+_4") (pintype "power_in"))
      (node (ref "IC4") (pin "11") (pinfunction "V+_11") (pintype "power_in"))
      (node (ref "R13") (pin "1") (pinfunction "1_1") (pintype "passive"))
      (node (ref "R19") (pin "1") (pinfunction "1_1") (pintype "passive"))
      (node (ref "R26") (pin "1") (pinfunction "1_1") (pintype "passive"))
      (node (ref "R3") (pin "1") (pinfunction "1_1") (pintype "passive"))
      (node (ref "R35") (pin "1") (pinfunction "1_1") (pintype "passive"))
      (node (ref "R39") (pin "1") (pinfunction "1_1") (pintype "passive"))
      (node (ref "R41") (pin "1") (pinfunction "1_1") (pintype "passive"))
      (node (ref "R42") (pin "2") (pinfunction "2_2") (pintype "passive"))
      (node (ref "R43") (pin "2") (pinfunction "2_2") (pintype "passive"))
      (node (ref "R55") (pin "2") (pinfunction "2_2") (pintype "passive"))
      (node (ref "R7") (pin "1") (pinfunction "1_1") (pintype "passive"))
      (node (ref "T9") (pin "3") (pinfunction "C_3") (pintype "passive"))
      (node (ref "U_FREQ_POT") (pin "P$4") (pinfunction "E_P$4") (pintype "passive"))
    )
    (net (code "73") (name "V-") (class "Default")
      (node (ref "C1") (pin "-") (pinfunction "-_-") (pintype "passive"))
      (node (ref "C14") (pin "1") (pinfunction "1_1") (pintype "passive"))
      (node (ref "C19") (pin "1") (pinfunction "1_1") (pintype "passive"))
      (node (ref "C21") (pin "2") (pinfunction "2_2") (pintype "passive"))
      (node (ref "C22") (pin "1") (pinfunction "1_1") (pintype "passive"))
      (node (ref "C3") (pin "2") (pinfunction "2_2") (pintype "passive"))
      (node (ref "C6") (pin "1") (pinfunction "1_1") (pintype "passive"))
      (node (ref "F1") (pin "1") (pinfunction "1_1") (pintype "passive"))
      (node (ref "IC1") (pin "11") (pinfunction "V-_11") (pintype "power_in"))
      (node (ref "IC2") (pin "4") (pinfunction "V-_4") (pintype "power_in"))
      (node (ref "IC3") (pin "11") (pinfunction "V-_11") (pintype "power_in"))
      (node (ref "IC4") (pin "6") (pinfunction "V-_6") (pintype "power_in"))
      (node (ref "R51") (pin "1") (pinfunction "1_1") (pintype "passive"))
      (node (ref "R56") (pin "2") (pinfunction "2_2") (pintype "passive"))
      (node (ref "T8") (pin "3") (pinfunction "C_3") (pintype "passive"))
      (node (ref "U_FREQ_POT") (pin "P$6") (pinfunction "A_P$6") (pintype "passive"))
    )
    (net (code "74") (name "unconnected-(IC4A-B-Pad7)") (class "Default")
      (node (ref "IC4") (pin "7") (pinfunction "B_7") (pintype "passive"))
    )
    (net (code "75") (name "unconnected-(IC4A-E-Pad8)") (class "Default")
      (node (ref "IC4") (pin "8") (pinfunction "E_8") (pintype "passive"))
    )
    (net (code "76") (name "unconnected-(IC4B-B-Pad10)") (class "Default")
      (node (ref "IC4") (pin "10") (pinfunction "B_10") (pintype "passive"))
    )
    (net (code "77") (name "unconnected-(IC4B-E-Pad9)") (class "Default")
      (node (ref "IC4") (pin "9") (pinfunction "E_9") (pintype "passive"))
    )
    (net (code "78") (name "unconnected-(TR1-PadA)") (class "Default")
      (node (ref "TR1") (pin "A") (pinfunction "A_A") (pintype "passive"))
    )
    (net (code "79") (name "unconnected-(TR2-PadE)") (class "Default")
      (node (ref "TR2") (pin "E") (pinfunction "E_E") (pintype "passive"))
    )
    (net (code "80") (name "unconnected-(TR3-PadE)") (class "Default")
      (node (ref "TR3") (pin "E") (pinfunction "E_E") (pintype "passive"))
    )
    (net (code "81") (name "unconnected-(TR4-PadE)") (class "Default")
      (node (ref "TR4") (pin "E") (pinfunction "E_E") (pintype "passive"))
    )
  )
)
